# inj_meas.net
KiCad netlist of a schematic drawn in Altium Designer
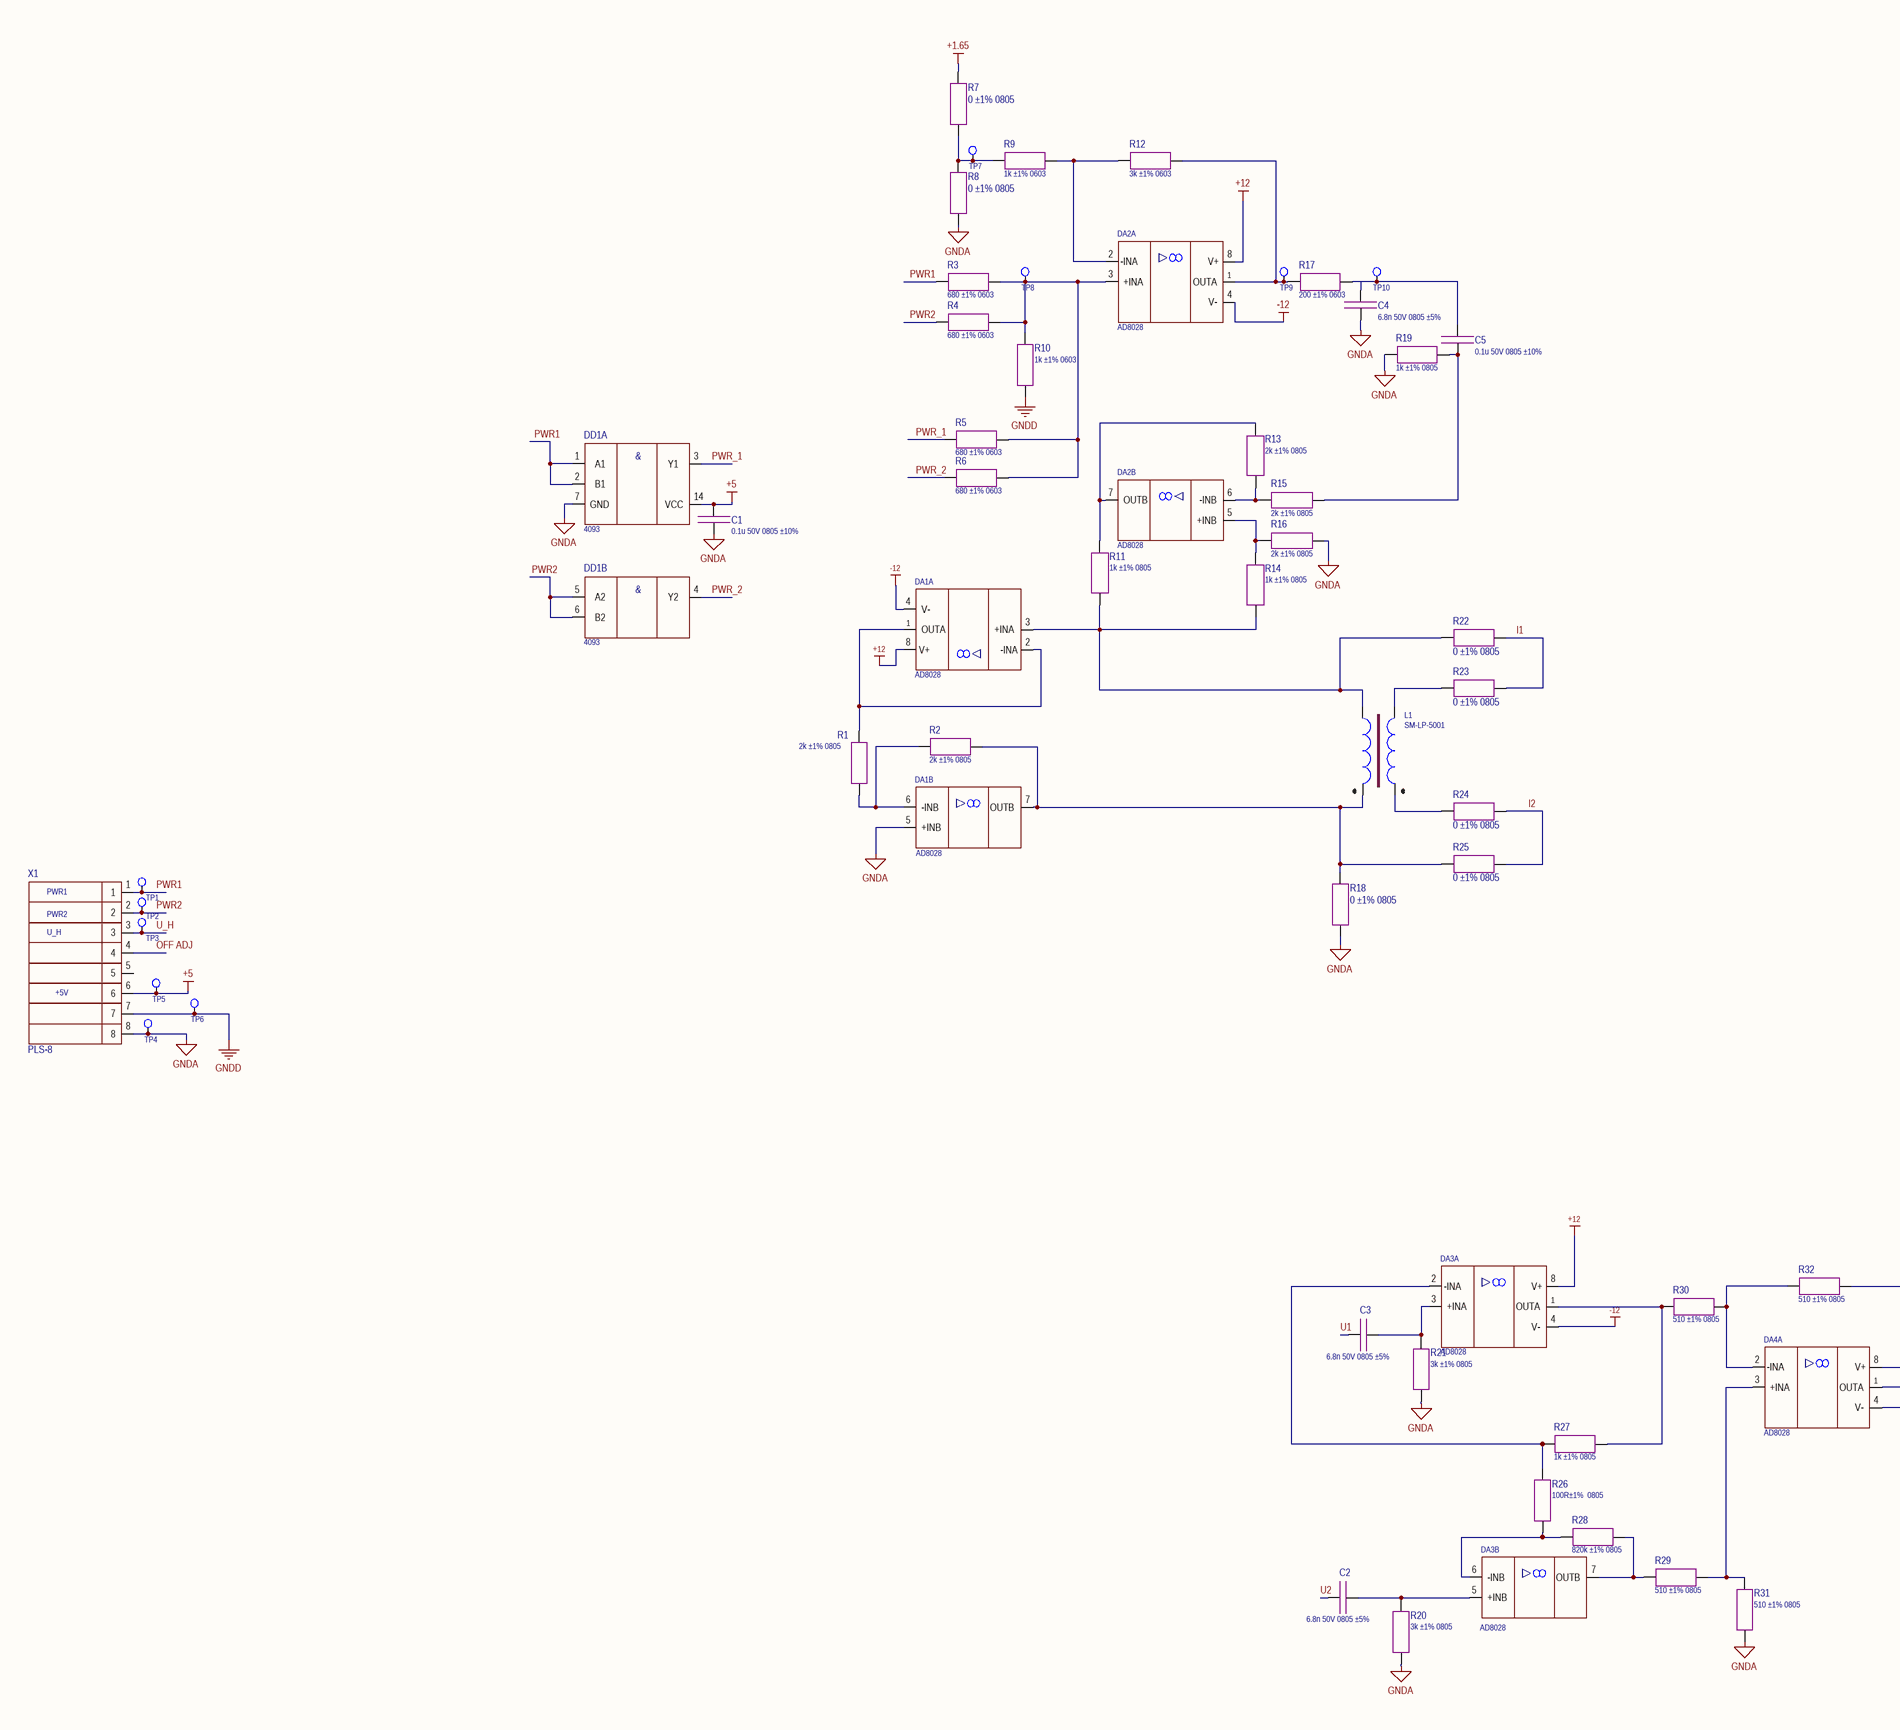
[diagram p0: inj_meas.SchDoc, left]
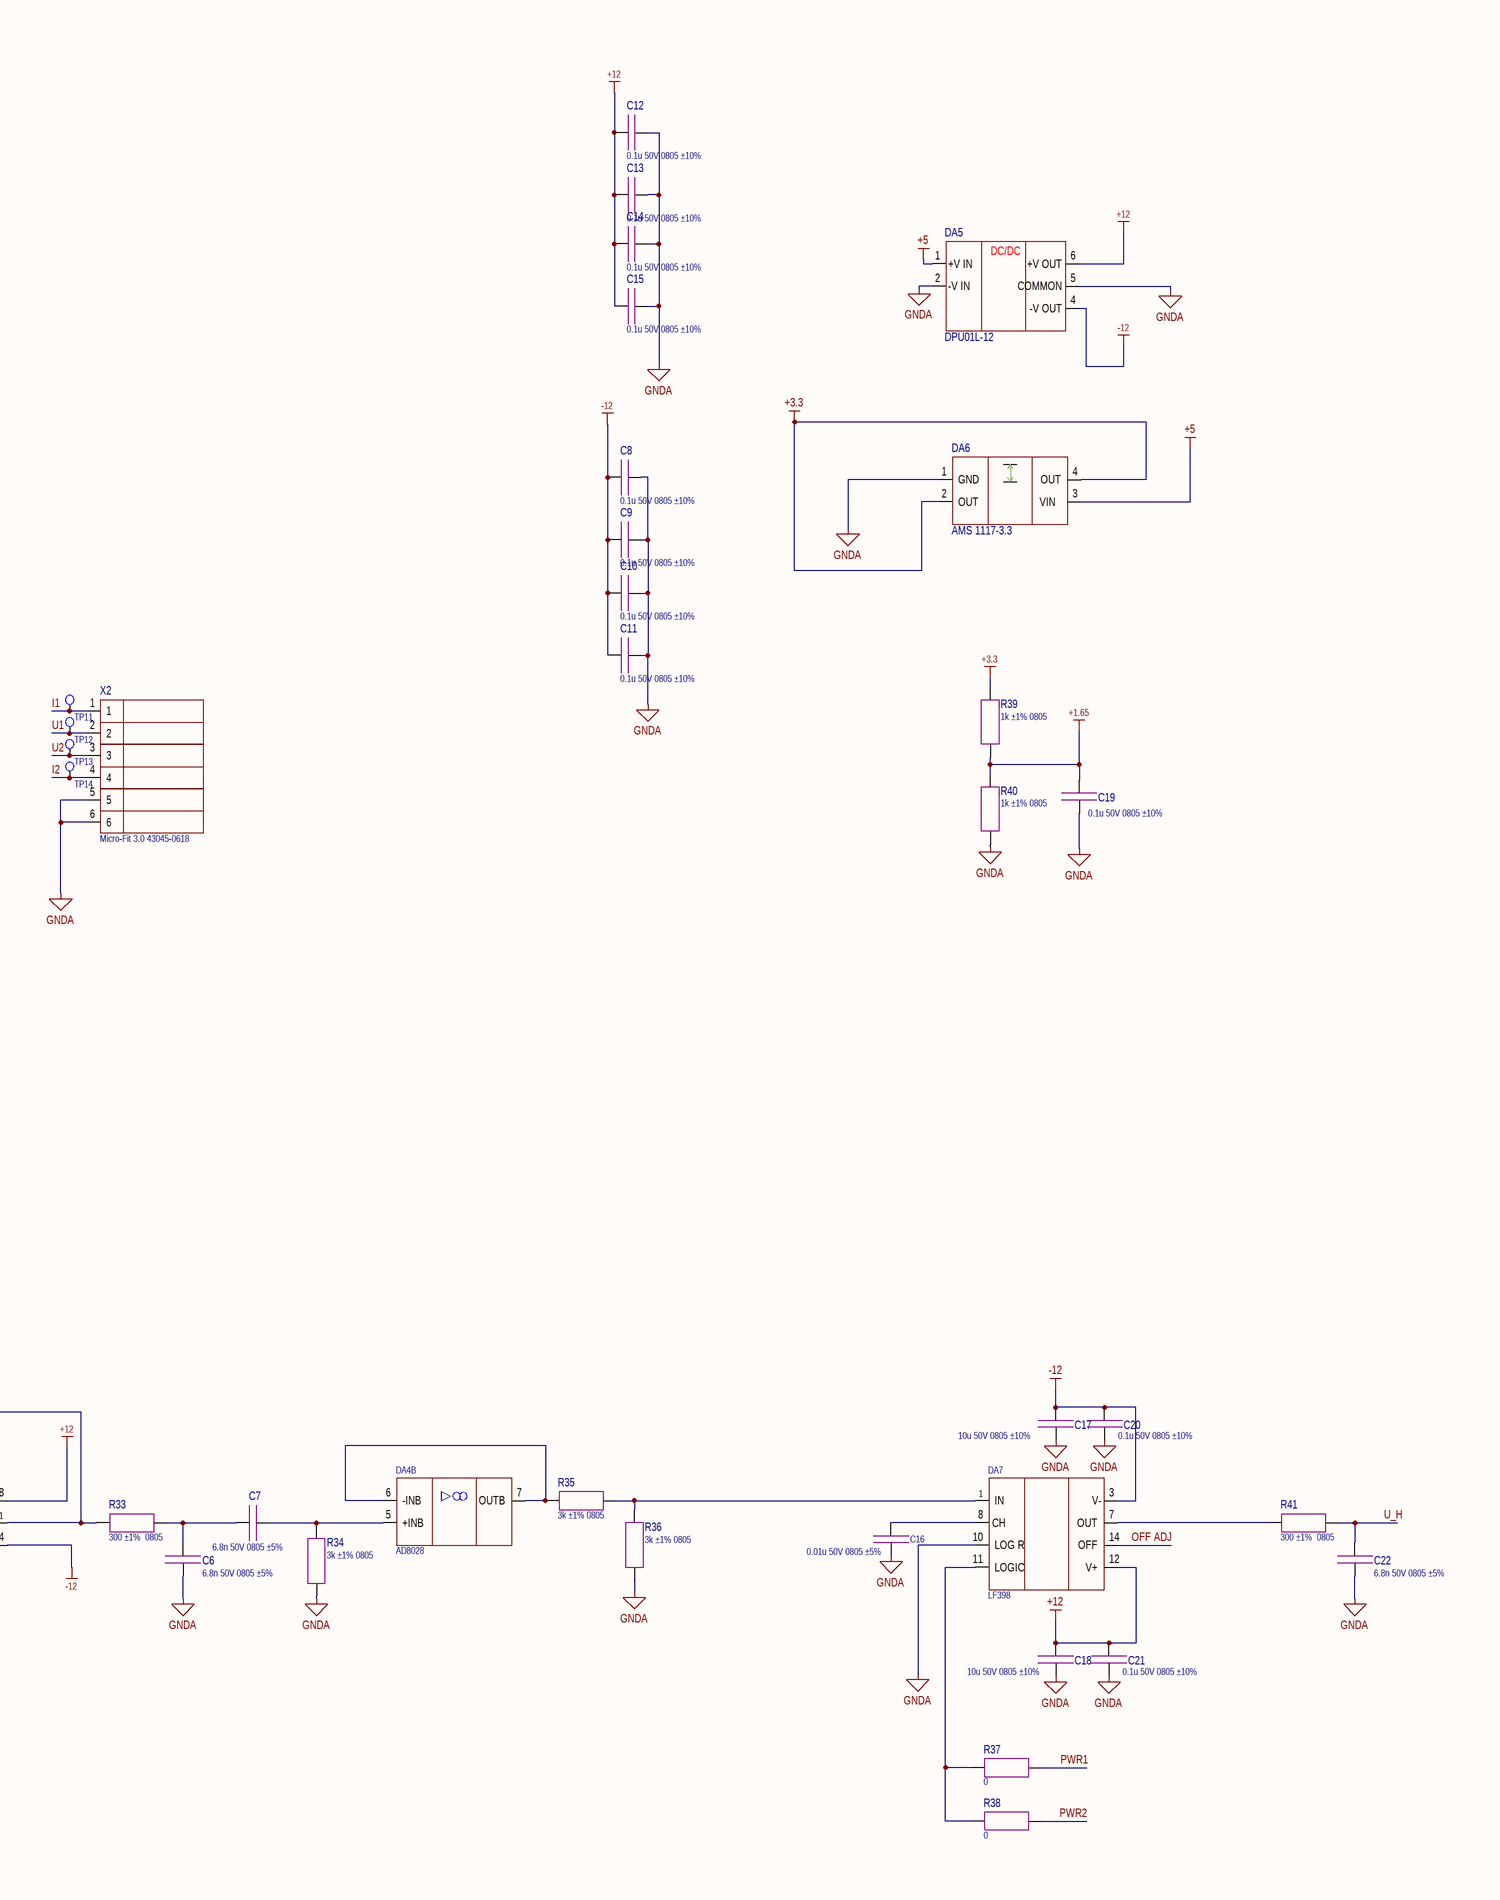
[diagram p1: inj_meas.SchDoc, right]

(export (version "E")
  (design (tool "Eeschema 10.0.6"))
  (components
    (comp (ref "C1")
      (value "0.1u 50V 0805 ±10%")
      (footprint "CAP: SMD 0805 MD IPC 782")
      (libsource (lib "UOMP capacitors") (part "0.1u 50V 0805 ±10%"))
    )
    (comp (ref "C2")
      (value "6.8n 50V 0805 ±5%")
      (footprint "CAP: SMD 0805 MD IPC 782")
      (libsource (lib "UOMP_capacitors") (part "6.8n 50V 0805 ±5%"))
    )
    (comp (ref "C3")
      (value "6.8n 50V 0805 ±5%")
      (footprint "CAP: SMD 0805 MD IPC 782")
      (libsource (lib "UOMP_capacitors") (part "6.8n 50V 0805 ±5%"))
    )
    (comp (ref "C4")
      (value "6.8n 50V 0805 ±5%")
      (footprint "CAP: SMD 0805 MD IPC 782")
      (libsource (lib "UOMP_capacitors") (part "6.8n 50V 0805 ±5%"))
    )
    (comp (ref "C5")
      (value "0.1u 50V 0805 ±10%")
      (footprint "CAP: SMD 0805 MD IPC 782")
      (libsource (lib "UOMP_capacitors") (part "0.1u 50V 0805 ±10%"))
    )
    (comp (ref "C6")
      (value "6.8n 50V 0805 ±5%")
      (footprint "CAP: SMD 0805 MD IPC 782")
      (libsource (lib "UOMP_capacitors") (part "6.8n 50V 0805 ±5%"))
    )
    (comp (ref "C7")
      (value "6.8n 50V 0805 ±5%")
      (footprint "CAP: SMD 0805 MD IPC 782")
      (libsource (lib "UOMP_capacitors") (part "6.8n 50V 0805 ±5%"))
    )
    (comp (ref "C8")
      (value "0.1u 50V 0805 ±10%")
      (footprint "CAP: SMD 0805 MD IPC 782")
      (libsource (lib "UOMP capacitors") (part "0.1u 50V 0805 ±10%"))
    )
    (comp (ref "C9")
      (value "0.1u 50V 0805 ±10%")
      (footprint "CAP: SMD 0805 MD IPC 782")
      (libsource (lib "UOMP capacitors") (part "0.1u 50V 0805 ±10%"))
    )
    (comp (ref "C10")
      (value "0.1u 50V 0805 ±10%")
      (footprint "CAP: SMD 0805 MD IPC 782")
      (libsource (lib "UOMP capacitors") (part "0.1u 50V 0805 ±10%"))
    )
    (comp (ref "C11")
      (value "0.1u 50V 0805 ±10%")
      (footprint "CAP: SMD 0805 MD IPC 782")
      (libsource (lib "UOMP capacitors") (part "0.1u 50V 0805 ±10%"))
    )
    (comp (ref "C12")
      (value "0.1u 50V 0805 ±10%")
      (footprint "CAP: SMD 0805 MD IPC 782")
      (libsource (lib "UOMP capacitors") (part "0.1u 50V 0805 ±10%"))
    )
    (comp (ref "C13")
      (value "0.1u 50V 0805 ±10%")
      (footprint "CAP: SMD 0805 MD IPC 782")
      (libsource (lib "UOMP capacitors") (part "0.1u 50V 0805 ±10%"))
    )
    (comp (ref "C14")
      (value "0.1u 50V 0805 ±10%")
      (footprint "CAP: SMD 0805 MD IPC 782")
      (libsource (lib "UOMP capacitors") (part "0.1u 50V 0805 ±10%"))
    )
    (comp (ref "C15")
      (value "0.1u 50V 0805 ±10%")
      (footprint "CAP: SMD 0805 MD IPC 782")
      (libsource (lib "UOMP capacitors") (part "0.1u 50V 0805 ±10%"))
    )
    (comp (ref "C16")
      (value "0.01u 50V 0805 ±5%")
      (footprint "CAP: SMD 0805 MD IPC 782")
      (libsource (lib "UOMP_capacitors") (part "0.01u 50V 0805 ±5%"))
    )
    (comp (ref "C17")
      (value "10u 50V 0805 ±10%")
      (footprint "CAP: SMD 0805 MD IPC 782")
      (libsource (lib "UOMP_capacitors") (part "10u 50V 0805 ±10%"))
    )
    (comp (ref "C18")
      (value "10u 50V 0805 ±10%")
      (footprint "CAP: SMD 0805 MD IPC 782")
      (libsource (lib "UOMP_capacitors") (part "10u 50V 0805 ±10%"))
    )
    (comp (ref "C19")
      (value "0.1u 50V 0805 ±10%")
      (footprint "CAP: SMD 0805 MD IPC 782")
      (libsource (lib "UOMP capacitors") (part "0.1u 50V 0805 ±10%"))
    )
    (comp (ref "C20")
      (value "0.1u 50V 0805 ±10%")
      (footprint "CAP: SMD 0805 MD IPC 782")
      (libsource (lib "UOMP_capacitors") (part "0.1u 50V 0805 ±10%"))
    )
    (comp (ref "C21")
      (value "0.1u 50V 0805 ±10%")
      (footprint "CAP: SMD 0805 MD IPC 782")
      (libsource (lib "UOMP_capacitors") (part "0.1u 50V 0805 ±10%"))
    )
    (comp (ref "C22")
      (value "6.8n 50V 0805 ±5%")
      (footprint "CAP: SMD 0805 MD IPC 782")
      (libsource (lib "UOMP_capacitors") (part "6.8n 50V 0805 ±5%"))
    )
    (comp (ref "DA1")
      (value "AD8028")
      (footprint "IC: SOIC 8")
      (libsource (lib "THE_BOYS_REO") (part "AD8028_part"))
    )
    (comp (ref "DA2") (value "AD8028") (footprint "IC: SOIC 8") (libsource (lib "") (part "AD8028_part_1")))
    (comp (ref "DA3")
      (value "AD8028")
      (footprint "IC: SOIC 8")
      (libsource (lib "THE_BOYS_REO") (part "AD8028_part"))
    )
    (comp (ref "DA4")
      (value "AD8028")
      (footprint "IC: SOIC 8")
      (libsource (lib "THE_BOYS_REO") (part "AD8028_part"))
    )
    (comp (ref "DA5")
      (value "DPU01L-12")
      (footprint "SIP-6")
      (libsource (lib "UOMP_power") (part "DC-DC{colon} +12/-12V DPU01L-12"))
    )
    (comp (ref "DA6")
      (value "AMS 1117-3.3")
      (footprint "IC: SOT 223")
      (libsource (lib "UOMP_power") (part "LDO{colon} 15-3.3V AMS1117"))
    )
    (comp (ref "DA7")
      (value "LF398")
      (footprint "IC: SOIC 14")
      (libsource (lib "THE_BOYS_REO") (part "LF398MX"))
    )
    (comp (ref "DD1")
      (value "4093")
      (footprint "IC: SOIC 14")
      (description "&")
      (libsource (lib "UOMP_IC") (part "LOGIC{colon} 4093"))
    )
    (comp (ref "L1")
      (value "SM-LP-5001")
      (footprint "IND: SM-LP-5001E")
      (libsource (lib "THE_BOYS_REO") (part "SM-LP-5001"))
    )
    (comp (ref "R1")
      (value "2k ±1% 0805")
      (footprint "RES: SMD 0805 MD IPC 782")
      (libsource (lib "UOMP resistors") (part "2k ±1% 0805"))
    )
    (comp (ref "R2")
      (value "2k ±1% 0805")
      (footprint "RES: SMD 0805 MD IPC 782")
      (libsource (lib "UOMP resistors") (part "2k ±1% 0805"))
    )
    (comp (ref "R3")
      (value "680 ±1% 0603")
      (footprint "RES: SMD 0603 MD IPC 782")
      (libsource (lib "UOMP_resistors") (part "680 ±1% 0603"))
    )
    (comp (ref "R4")
      (value "680 ±1% 0603")
      (footprint "RES: SMD 0603 MD IPC 782")
      (libsource (lib "UOMP_resistors") (part "680 ±1% 0603"))
    )
    (comp (ref "R5")
      (value "680 ±1% 0603")
      (footprint "RES: SMD 0603 MD IPC 782")
      (libsource (lib "UOMP_resistors") (part "680 ±1% 0603"))
    )
    (comp (ref "R6")
      (value "680 ±1% 0603")
      (footprint "RES: SMD 0603 MD IPC 782")
      (libsource (lib "UOMP_resistors") (part "680 ±1% 0603"))
    )
    (comp (ref "R7")
      (value "0 ±1% 0805")
      (footprint "RES: SMD 0805 MD IPC 782")
      (libsource (lib "UOMP_resistors") (part "0 ±1% 0805"))
    )
    (comp (ref "R8")
      (value "0 ±1% 0805")
      (footprint "RES: SMD 0805 MD IPC 782")
      (libsource (lib "UOMP_resistors") (part "0 ±1% 0805"))
    )
    (comp (ref "R9")
      (value "1k ±1% 0603")
      (footprint "RES: SMD 0603 MD IPC 782")
      (libsource (lib "UOMP_resistors") (part "1k ±1% 0603"))
    )
    (comp (ref "R10")
      (value "1k ±1% 0603")
      (footprint "RES: SMD 0603 MD IPC 782")
      (libsource (lib "UOMP_resistors") (part "1k ±1% 0603"))
    )
    (comp (ref "R11")
      (value "1k ±1% 0805")
      (footprint "RES: SMD 0805 MD IPC 782")
      (libsource (lib "UOMP resistors") (part "1k ±1% 0805"))
    )
    (comp (ref "R12")
      (value "3k ±1% 0603")
      (footprint "RES: SMD 0603 MD IPC 782")
      (libsource (lib "UOMP_resistors") (part "3k ±1% 0603"))
    )
    (comp (ref "R13")
      (value "2k ±1% 0805")
      (footprint "RES: SMD 0805 MD IPC 782")
      (libsource (lib "UOMP resistors") (part "2k ±1% 0805"))
    )
    (comp (ref "R14")
      (value "1k ±1% 0805")
      (footprint "RES: SMD 0805 MD IPC 782")
      (libsource (lib "UOMP resistors") (part "1k ±1% 0805"))
    )
    (comp (ref "R15")
      (value "2k ±1% 0805")
      (footprint "RES: SMD 0805 MD IPC 782")
      (libsource (lib "UOMP resistors") (part "2k ±1% 0805"))
    )
    (comp (ref "R16")
      (value "2k ±1% 0805")
      (footprint "RES: SMD 0805 MD IPC 782")
      (libsource (lib "UOMP resistors") (part "2k ±1% 0805"))
    )
    (comp (ref "R17")
      (value "200 ±1% 0603")
      (footprint "RES: SMD 0603 MD IPC 782")
      (libsource (lib "UOMP_resistors") (part "200 ±1% 0603"))
    )
    (comp (ref "R18")
      (value "0 ±1% 0805")
      (footprint "RES: SMD 0805 MD IPC 782")
      (libsource (lib "UOMP_resistors") (part "0 ±1% 0805"))
    )
    (comp (ref "R19")
      (value "1k ±1% 0805")
      (footprint "RES: SMD 0805 MD IPC 782")
      (libsource (lib "UOMP_resistors") (part "1k ±1% 0805"))
    )
    (comp (ref "R20")
      (value "3k ±1% 0805")
      (footprint "RES: SMD 0805 MD IPC 782")
      (libsource (lib "UOMP_resistors") (part "3k ±1% 0805"))
    )
    (comp (ref "R21")
      (value "3k ±1% 0805")
      (footprint "RES: SMD 0805 MD IPC 782")
      (libsource (lib "UOMP_resistors") (part "3k ±1% 0805"))
    )
    (comp (ref "R22")
      (value "0 ±1% 0805")
      (footprint "RES: SMD 0805 MD IPC 782")
      (libsource (lib "UOMP_resistors") (part "0 ±1% 0805"))
    )
    (comp (ref "R23")
      (value "0 ±1% 0805")
      (footprint "RES: SMD 0805 MD IPC 782")
      (libsource (lib "UOMP_resistors") (part "0 ±1% 0805"))
    )
    (comp (ref "R24")
      (value "0 ±1% 0805")
      (footprint "RES: SMD 0805 MD IPC 782")
      (libsource (lib "UOMP_resistors") (part "0 ±1% 0805"))
    )
    (comp (ref "R25")
      (value "0 ±1% 0805")
      (footprint "RES: SMD 0805 MD IPC 782")
      (libsource (lib "UOMP_resistors") (part "0 ±1% 0805"))
    )
    (comp (ref "R26")
      (value "100R±1%  0805")
      (footprint "RES: SMD 0805 MD IPC 782")
      (libsource (lib "UOMP_resistors") (part "100 ±1%  0805"))
    )
    (comp (ref "R27")
      (value "1k ±1% 0805")
      (footprint "RES: SMD 0805 MD IPC 782")
      (libsource (lib "UOMP_resistors") (part "1k ±1% 0805"))
    )
    (comp (ref "R28")
      (value "820k ±1% 0805")
      (footprint "RES: SMD 0805 MD IPC 782")
      (libsource (lib "UOMP_resistors") (part "820k ±1% 0805"))
    )
    (comp (ref "R29")
      (value "510 ±1% 0805")
      (footprint "RES: SMD 0805 MD IPC 782")
      (libsource (lib "UOMP_resistors") (part "510 ±1% 0805"))
    )
    (comp (ref "R30")
      (value "510 ±1% 0805")
      (footprint "RES: SMD 0805 MD IPC 782")
      (libsource (lib "UOMP_resistors") (part "510 ±1% 0805"))
    )
    (comp (ref "R31")
      (value "510 ±1% 0805")
      (footprint "RES: SMD 0805 MD IPC 782")
      (libsource (lib "UOMP_resistors") (part "510 ±1% 0805"))
    )
    (comp (ref "R32")
      (value "510 ±1% 0805")
      (footprint "RES: SMD 0805 MD IPC 782")
      (libsource (lib "UOMP_resistors") (part "510 ±1% 0805"))
    )
    (comp (ref "R33")
      (value "300 ±1%  0805")
      (footprint "RES: SMD 0805 MD IPC 782")
      (libsource (lib "UOMP_resistors") (part "300 ±1%  0805"))
    )
    (comp (ref "R34")
      (value "3k ±1% 0805")
      (footprint "RES: SMD 0805 MD IPC 782")
      (libsource (lib "UOMP_resistors") (part "3k ±1% 0805"))
    )
    (comp (ref "R35")
      (value "3k ±1% 0805")
      (footprint "RES: SMD 0805 MD IPC 782")
      (libsource (lib "UOMP_resistors") (part "3k ±1% 0805"))
    )
    (comp (ref "R36")
      (value "3k ±1% 0805")
      (footprint "RES: SMD 0805 MD IPC 782")
      (libsource (lib "UOMP_resistors") (part "3k ±1% 0805"))
    )
    (comp (ref "R37")
      (value "0")
      (footprint "RES: SMD 0603 MD IPC 782")
      (libsource (lib "UOMP_resistors_0603") (part "0 ±5%"))
    )
    (comp (ref "R38")
      (value "0")
      (footprint "RES: SMD 0603 MD IPC 782")
      (libsource (lib "UOMP_resistors_0603") (part "0 ±5%"))
    )
    (comp (ref "R39")
      (value "1k ±1% 0805")
      (footprint "RES: SMD 0805 MD IPC 782")
      (libsource (lib "UOMP resistors") (part "1k ±1% 0805"))
    )
    (comp (ref "R40")
      (value "1k ±1% 0805")
      (footprint "RES: SMD 0805 MD IPC 782")
      (libsource (lib "UOMP resistors") (part "1k ±1% 0805"))
    )
    (comp (ref "R41")
      (value "300 ±1%  0805")
      (footprint "RES: SMD 0805 MD IPC 782")
      (libsource (lib "UOMP_resistors") (part "300 ±1%  0805"))
    )
    (comp (ref "TP1")
      (value "Test point")
      (footprint "Test Point")
      (libsource (lib "UOMP_primitives") (part "Test point"))
    )
    (comp (ref "TP2")
      (value "Test point")
      (footprint "Test Point")
      (libsource (lib "UOMP_primitives") (part "Test point"))
    )
    (comp (ref "TP3")
      (value "Test point")
      (footprint "Test Point")
      (libsource (lib "UOMP_primitives") (part "Test point"))
    )
    (comp (ref "TP4")
      (value "Test point")
      (footprint "Test Point")
      (libsource (lib "UOMP_primitives") (part "Test point"))
    )
    (comp (ref "TP5")
      (value "Test point")
      (footprint "Test Point")
      (libsource (lib "UOMP_primitives") (part "Test point"))
    )
    (comp (ref "TP6")
      (value "Test point")
      (footprint "Test Point")
      (libsource (lib "UOMP_primitives") (part "Test point"))
    )
    (comp (ref "TP7")
      (value "Test point")
      (footprint "Test Point")
      (libsource (lib "UOMP_primitives") (part "Test point"))
    )
    (comp (ref "TP8")
      (value "Test point")
      (footprint "Test Point")
      (libsource (lib "UOMP_primitives") (part "Test point"))
    )
    (comp (ref "TP9")
      (value "Test point")
      (footprint "Test Point")
      (libsource (lib "UOMP_primitives") (part "Test point"))
    )
    (comp (ref "TP10")
      (value "Test point")
      (footprint "Test Point")
      (libsource (lib "UOMP_primitives") (part "Test point"))
    )
    (comp (ref "TP11")
      (value "Test point")
      (footprint "Test Point")
      (libsource (lib "UOMP_primitives") (part "Test point"))
    )
    (comp (ref "TP12")
      (value "Test point")
      (footprint "Test Point")
      (libsource (lib "UOMP_primitives") (part "Test point"))
    )
    (comp (ref "TP13")
      (value "Test point")
      (footprint "Test Point")
      (libsource (lib "UOMP_primitives") (part "Test point"))
    )
    (comp (ref "TP14")
      (value "Test point")
      (footprint "Test Point")
      (libsource (lib "UOMP_primitives") (part "Test point"))
    )
    (comp (ref "X1")
      (value "PLS-8")
      (footprint "CON: 8PIN PLS-8")
      (libsource (lib "UOMP_connectors") (part "8 pin PLS 8"))
    )
    (comp (ref "X2")
      (value "Micro-Fit 3.0 43045-0618")
      (footprint "CON: 6pin Molex MicroFit 3.0 43045-0618")
      (libsource (lib "UOMP_connectors") (part "6 pin MicroFit DR SMD Molex"))
    )
  )
  (nets
    (net (code "1") (name "+1.65") (class "Default")
      (node (ref "C19") (pin "1") (pinfunction "1_1") (pintype "passive"))
      (node (ref "R39") (pin "1") (pinfunction "1_1") (pintype "passive"))
      (node (ref "R40") (pin "2") (pinfunction "2_2") (pintype "passive"))
      (node (ref "R7") (pin "2") (pinfunction "2_2") (pintype "passive"))
    )
    (net (code "2") (name "+3.3") (class "Default")
      (node (ref "DA6") (pin "2") (pinfunction "OUT_2") (pintype "passive"))
      (node (ref "DA6") (pin "4") (pinfunction "OUT_4") (pintype "passive"))
      (node (ref "R39") (pin "2") (pinfunction "2_2") (pintype "passive"))
    )
    (net (code "3") (name "+5") (class "Default")
      (node (ref "C1") (pin "1") (pinfunction "1_1") (pintype "passive"))
      (node (ref "DA5") (pin "1") (pinfunction "+V_IN_1") (pintype "passive"))
      (node (ref "DA6") (pin "3") (pinfunction "VIN_3") (pintype "passive"))
      (node (ref "DD1") (pin "14") (pinfunction "VCC_14") (pintype "passive"))
      (node (ref "TP5") (pin "1") (pinfunction "1_1") (pintype "passive"))
      (node (ref "X1") (pin "6") (pinfunction "6_6") (pintype "passive"))
    )
    (net (code "4") (name "+12") (class "Default")
      (node (ref "C12") (pin "2") (pinfunction "2_2") (pintype "passive"))
      (node (ref "C13") (pin "2") (pinfunction "2_2") (pintype "passive"))
      (node (ref "C14") (pin "2") (pinfunction "2_2") (pintype "passive"))
      (node (ref "C15") (pin "2") (pinfunction "2_2") (pintype "passive"))
      (node (ref "C18") (pin "1") (pinfunction "1_1") (pintype "passive"))
      (node (ref "C21") (pin "1") (pinfunction "1_1") (pintype "passive"))
      (node (ref "DA1") (pin "8") (pinfunction "V+_8") (pintype "passive"))
      (node (ref "DA2") (pin "8") (pinfunction "V+_8") (pintype "passive"))
      (node (ref "DA3") (pin "8") (pinfunction "V+_8") (pintype "passive"))
      (node (ref "DA4") (pin "8") (pinfunction "V+_8") (pintype "passive"))
      (node (ref "DA5") (pin "6") (pinfunction "+V_OUT_6") (pintype "passive"))
      (node (ref "DA7") (pin "12") (pinfunction "V+_12") (pintype "passive"))
    )
    (net (code "5") (name "-12") (class "Default")
      (node (ref "C10") (pin "2") (pinfunction "2_2") (pintype "passive"))
      (node (ref "C11") (pin "2") (pinfunction "2_2") (pintype "passive"))
      (node (ref "C17") (pin "1") (pinfunction "1_1") (pintype "passive"))
      (node (ref "C20") (pin "1") (pinfunction "1_1") (pintype "passive"))
      (node (ref "C8") (pin "2") (pinfunction "2_2") (pintype "passive"))
      (node (ref "C9") (pin "2") (pinfunction "2_2") (pintype "passive"))
      (node (ref "DA1") (pin "4") (pinfunction "V-_4") (pintype "passive"))
      (node (ref "DA2") (pin "4") (pinfunction "V-_4") (pintype "passive"))
      (node (ref "DA3") (pin "4") (pinfunction "V-_4") (pintype "passive"))
      (node (ref "DA4") (pin "4") (pinfunction "V-_4") (pintype "passive"))
      (node (ref "DA5") (pin "4") (pinfunction "-V_OUT_4") (pintype "passive"))
      (node (ref "DA7") (pin "3") (pinfunction "V-_3") (pintype "passive"))
    )
    (net (code "6") (name "/I1") (class "Default")
      (node (ref "R22") (pin "2") (pinfunction "2_2") (pintype "passive"))
      (node (ref "R23") (pin "2") (pinfunction "2_2") (pintype "passive"))
      (node (ref "TP11") (pin "1") (pinfunction "1_1") (pintype "passive"))
      (node (ref "X2") (pin "1") (pinfunction "1_1") (pintype "passive"))
    )
    (net (code "7") (name "/I2") (class "Default")
      (node (ref "R24") (pin "2") (pinfunction "2_2") (pintype "passive"))
      (node (ref "R25") (pin "2") (pinfunction "2_2") (pintype "passive"))
      (node (ref "TP14") (pin "1") (pinfunction "1_1") (pintype "passive"))
      (node (ref "X2") (pin "4") (pinfunction "4_4") (pintype "passive"))
    )
    (net (code "8") (name "/OFF ADJ") (class "Default")
      (node (ref "DA7") (pin "14") (pinfunction "OFF_14") (pintype "passive"))
      (node (ref "X1") (pin "4") (pinfunction "4_4") (pintype "passive"))
    )
    (net (code "9") (name "/PWR1") (class "Default")
      (node (ref "DD1") (pin "1") (pinfunction "A1_1") (pintype "passive"))
      (node (ref "DD1") (pin "2") (pinfunction "B1_2") (pintype "passive"))
      (node (ref "R3") (pin "1") (pinfunction "1_1") (pintype "passive"))
      (node (ref "R37") (pin "2") (pinfunction "2_2") (pintype "passive"))
      (node (ref "TP1") (pin "1") (pinfunction "1_1") (pintype "passive"))
      (node (ref "X1") (pin "1") (pinfunction "1_1") (pintype "passive"))
    )
    (net (code "10") (name "/PWR2") (class "Default")
      (node (ref "DD1") (pin "5") (pinfunction "A2_5") (pintype "passive"))
      (node (ref "DD1") (pin "6") (pinfunction "B2_6") (pintype "passive"))
      (node (ref "R38") (pin "2") (pinfunction "2_2") (pintype "passive"))
      (node (ref "R4") (pin "1") (pinfunction "1_1") (pintype "passive"))
      (node (ref "TP2") (pin "1") (pinfunction "1_1") (pintype "passive"))
      (node (ref "X1") (pin "2") (pinfunction "2_2") (pintype "passive"))
    )
    (net (code "11") (name "/PWR_1") (class "Default")
      (node (ref "DD1") (pin "3") (pinfunction "Y1_3") (pintype "passive"))
      (node (ref "R5") (pin "1") (pinfunction "1_1") (pintype "passive"))
    )
    (net (code "12") (name "/PWR_2") (class "Default")
      (node (ref "DD1") (pin "4") (pinfunction "Y2_4") (pintype "passive"))
      (node (ref "R6") (pin "1") (pinfunction "1_1") (pintype "passive"))
    )
    (net (code "13") (name "/U1") (class "Default")
      (node (ref "C3") (pin "2") (pinfunction "2_2") (pintype "passive"))
      (node (ref "TP12") (pin "1") (pinfunction "1_1") (pintype "passive"))
      (node (ref "X2") (pin "2") (pinfunction "2_2") (pintype "passive"))
    )
    (net (code "14") (name "/U2") (class "Default")
      (node (ref "C2") (pin "2") (pinfunction "2_2") (pintype "passive"))
      (node (ref "TP13") (pin "1") (pinfunction "1_1") (pintype "passive"))
      (node (ref "X2") (pin "3") (pinfunction "3_3") (pintype "passive"))
    )
    (net (code "15") (name "/U_H") (class "Default")
      (node (ref "C22") (pin "1") (pinfunction "1_1") (pintype "passive"))
      (node (ref "R41") (pin "2") (pinfunction "2_2") (pintype "passive"))
      (node (ref "TP3") (pin "1") (pinfunction "1_1") (pintype "passive"))
      (node (ref "X1") (pin "3") (pinfunction "3_3") (pintype "passive"))
    )
    (net (code "16") (name "GNDA") (class "Default")
      (node (ref "C1") (pin "2") (pinfunction "2_2") (pintype "passive"))
      (node (ref "C10") (pin "1") (pinfunction "1_1") (pintype "passive"))
      (node (ref "C11") (pin "1") (pinfunction "1_1") (pintype "passive"))
      (node (ref "C12") (pin "1") (pinfunction "1_1") (pintype "passive"))
      (node (ref "C13") (pin "1") (pinfunction "1_1") (pintype "passive"))
      (node (ref "C14") (pin "1") (pinfunction "1_1") (pintype "passive"))
      (node (ref "C15") (pin "1") (pinfunction "1_1") (pintype "passive"))
      (node (ref "C16") (pin "2") (pinfunction "2_2") (pintype "passive"))
      (node (ref "C17") (pin "2") (pinfunction "2_2") (pintype "passive"))
      (node (ref "C18") (pin "2") (pinfunction "2_2") (pintype "passive"))
      (node (ref "C19") (pin "2") (pinfunction "2_2") (pintype "passive"))
      (node (ref "C20") (pin "2") (pinfunction "2_2") (pintype "passive"))
      (node (ref "C21") (pin "2") (pinfunction "2_2") (pintype "passive"))
      (node (ref "C22") (pin "2") (pinfunction "2_2") (pintype "passive"))
      (node (ref "C4") (pin "2") (pinfunction "2_2") (pintype "passive"))
      (node (ref "C6") (pin "2") (pinfunction "2_2") (pintype "passive"))
      (node (ref "C8") (pin "1") (pinfunction "1_1") (pintype "passive"))
      (node (ref "C9") (pin "1") (pinfunction "1_1") (pintype "passive"))
      (node (ref "DA1") (pin "5") (pinfunction "+INB_5") (pintype "passive"))
      (node (ref "DA5") (pin "2") (pinfunction "-V_IN_2") (pintype "passive"))
      (node (ref "DA5") (pin "5") (pinfunction "COMMON_5") (pintype "passive"))
      (node (ref "DA6") (pin "1") (pinfunction "GND_1") (pintype "passive"))
      (node (ref "DA7") (pin "10") (pinfunction "LOG_R_10") (pintype "passive"))
      (node (ref "DD1") (pin "7") (pinfunction "GND_7") (pintype "passive"))
      (node (ref "R16") (pin "2") (pinfunction "2_2") (pintype "passive"))
      (node (ref "R18") (pin "1") (pinfunction "1_1") (pintype "passive"))
      (node (ref "R19") (pin "1") (pinfunction "1_1") (pintype "passive"))
      (node (ref "R20") (pin "2") (pinfunction "2_2") (pintype "passive"))
      (node (ref "R21") (pin "2") (pinfunction "2_2") (pintype "passive"))
      (node (ref "R31") (pin "1") (pinfunction "1_1") (pintype "passive"))
      (node (ref "R34") (pin "2") (pinfunction "2_2") (pintype "passive"))
      (node (ref "R36") (pin "1") (pinfunction "1_1") (pintype "passive"))
      (node (ref "R40") (pin "1") (pinfunction "1_1") (pintype "passive"))
      (node (ref "R8") (pin "1") (pinfunction "1_1") (pintype "passive"))
      (node (ref "TP4") (pin "1") (pinfunction "1_1") (pintype "passive"))
      (node (ref "X1") (pin "8") (pinfunction "8_8") (pintype "passive"))
      (node (ref "X2") (pin "5") (pinfunction "5_5") (pintype "passive"))
      (node (ref "X2") (pin "6") (pinfunction "6_6") (pintype "passive"))
    )
    (net (code "17") (name "GNDD") (class "Default")
      (node (ref "R10") (pin "1") (pinfunction "1_1") (pintype "passive"))
      (node (ref "TP6") (pin "1") (pinfunction "1_1") (pintype "passive"))
      (node (ref "X1") (pin "7") (pinfunction "7_7") (pintype "passive"))
    )
    (net (code "18") (name "Net-(C4-Pad1)") (class "Default")
      (node (ref "C4") (pin "1") (pinfunction "1_1") (pintype "passive"))
      (node (ref "C5") (pin "2") (pinfunction "2_2") (pintype "passive"))
      (node (ref "R17") (pin "2") (pinfunction "2_2") (pintype "passive"))
      (node (ref "TP10") (pin "1") (pinfunction "1_1") (pintype "passive"))
    )
    (net (code "19") (name "Net-(C5-Pad1)") (class "Default")
      (node (ref "C5") (pin "1") (pinfunction "1_1") (pintype "passive"))
      (node (ref "R15") (pin "2") (pinfunction "2_2") (pintype "passive"))
      (node (ref "R19") (pin "2") (pinfunction "2_2") (pintype "passive"))
    )
    (net (code "20") (name "Net-(C6-Pad1)") (class "Default")
      (node (ref "C6") (pin "1") (pinfunction "1_1") (pintype "passive"))
      (node (ref "C7") (pin "2") (pinfunction "2_2") (pintype "passive"))
      (node (ref "R33") (pin "2") (pinfunction "2_2") (pintype "passive"))
    )
    (net (code "21") (name "Net-(DA1A-+INA)") (class "Default")
      (node (ref "DA1") (pin "3") (pinfunction "+INA_3") (pintype "passive"))
      (node (ref "L1") (pin "4") (pinfunction "4_4") (pintype "passive"))
      (node (ref "R11") (pin "2") (pinfunction "2_2") (pintype "passive"))
      (node (ref "R14") (pin "1") (pinfunction "1_1") (pintype "passive"))
      (node (ref "R22") (pin "1") (pinfunction "1_1") (pintype "passive"))
    )
    (net (code "22") (name "Net-(DA1A--INA)") (class "Default")
      (node (ref "DA1") (pin "1") (pinfunction "OUTA_1") (pintype "passive"))
      (node (ref "DA1") (pin "2") (pinfunction "-INA_2") (pintype "passive"))
      (node (ref "R1") (pin "1") (pinfunction "1_1") (pintype "passive"))
    )
    (net (code "23") (name "Net-(DA1B--INB)") (class "Default")
      (node (ref "DA1") (pin "6") (pinfunction "-INB_6") (pintype "passive"))
      (node (ref "R1") (pin "2") (pinfunction "2_2") (pintype "passive"))
      (node (ref "R2") (pin "1") (pinfunction "1_1") (pintype "passive"))
    )
    (net (code "24") (name "Net-(DA1B-OUTB)") (class "Default")
      (node (ref "DA1") (pin "7") (pinfunction "OUTB_7") (pintype "passive"))
      (node (ref "L1") (pin "1") (pinfunction "3_1") (pintype "passive"))
      (node (ref "R18") (pin "2") (pinfunction "2_2") (pintype "passive"))
      (node (ref "R2") (pin "2") (pinfunction "2_2") (pintype "passive"))
      (node (ref "R25") (pin "1") (pinfunction "1_1") (pintype "passive"))
    )
    (net (code "25") (name "Net-(DA2A-+INA)") (class "Default")
      (node (ref "DA2") (pin "3") (pinfunction "+INA_3") (pintype "passive"))
      (node (ref "R10") (pin "2") (pinfunction "2_2") (pintype "passive"))
      (node (ref "R3") (pin "2") (pinfunction "2_2") (pintype "passive"))
      (node (ref "R4") (pin "2") (pinfunction "2_2") (pintype "passive"))
      (node (ref "R5") (pin "2") (pinfunction "2_2") (pintype "passive"))
      (node (ref "R6") (pin "2") (pinfunction "2_2") (pintype "passive"))
      (node (ref "TP8") (pin "1") (pinfunction "1_1") (pintype "passive"))
    )
    (net (code "26") (name "Net-(DA2A--INA)") (class "Default")
      (node (ref "DA2") (pin "2") (pinfunction "-INA_2") (pintype "passive"))
      (node (ref "R12") (pin "1") (pinfunction "1_1") (pintype "passive"))
      (node (ref "R9") (pin "2") (pinfunction "2_2") (pintype "passive"))
    )
    (net (code "27") (name "Net-(DA2A-OUTA)") (class "Default")
      (node (ref "DA2") (pin "1") (pinfunction "OUTA_1") (pintype "passive"))
      (node (ref "R12") (pin "2") (pinfunction "2_2") (pintype "passive"))
      (node (ref "R17") (pin "1") (pinfunction "1_1") (pintype "passive"))
      (node (ref "TP9") (pin "1") (pinfunction "1_1") (pintype "passive"))
    )
    (net (code "28") (name "Net-(DA2B-+INB)") (class "Default")
      (node (ref "DA2") (pin "5") (pinfunction "+INB_5") (pintype "passive"))
      (node (ref "R14") (pin "2") (pinfunction "2_2") (pintype "passive"))
      (node (ref "R16") (pin "1") (pinfunction "1_1") (pintype "passive"))
    )
    (net (code "29") (name "Net-(DA2B--INB)") (class "Default")
      (node (ref "DA2") (pin "6") (pinfunction "-INB_6") (pintype "passive"))
      (node (ref "R13") (pin "2") (pinfunction "2_2") (pintype "passive"))
      (node (ref "R15") (pin "1") (pinfunction "1_1") (pintype "passive"))
    )
    (net (code "30") (name "Net-(DA2B-OUTB)") (class "Default")
      (node (ref "DA2") (pin "7") (pinfunction "OUTB_7") (pintype "passive"))
      (node (ref "R11") (pin "1") (pinfunction "1_1") (pintype "passive"))
      (node (ref "R13") (pin "1") (pinfunction "1_1") (pintype "passive"))
    )
    (net (code "31") (name "Net-(DA3A-+INA)") (class "Default")
      (node (ref "C3") (pin "1") (pinfunction "1_1") (pintype "passive"))
      (node (ref "DA3") (pin "3") (pinfunction "+INA_3") (pintype "passive"))
      (node (ref "R21") (pin "1") (pinfunction "1_1") (pintype "passive"))
    )
    (net (code "32") (name "Net-(DA3A--INA)") (class "Default")
      (node (ref "DA3") (pin "2") (pinfunction "-INA_2") (pintype "passive"))
      (node (ref "R26") (pin "2") (pinfunction "2_2") (pintype "passive"))
      (node (ref "R27") (pin "2") (pinfunction "2_2") (pintype "passive"))
    )
    (net (code "33") (name "Net-(DA3A-OUTA)") (class "Default")
      (node (ref "DA3") (pin "1") (pinfunction "OUTA_1") (pintype "passive"))
      (node (ref "R27") (pin "1") (pinfunction "1_1") (pintype "passive"))
      (node (ref "R30") (pin "1") (pinfunction "1_1") (pintype "passive"))
    )
    (net (code "34") (name "Net-(DA3B-+INB)") (class "Default")
      (node (ref "C2") (pin "1") (pinfunction "1_1") (pintype "passive"))
      (node (ref "DA3") (pin "5") (pinfunction "+INB_5") (pintype "passive"))
      (node (ref "R20") (pin "1") (pinfunction "1_1") (pintype "passive"))
    )
    (net (code "35") (name "Net-(DA3B--INB)") (class "Default")
      (node (ref "DA3") (pin "6") (pinfunction "-INB_6") (pintype "passive"))
      (node (ref "R26") (pin "1") (pinfunction "1_1") (pintype "passive"))
      (node (ref "R28") (pin "2") (pinfunction "2_2") (pintype "passive"))
    )
    (net (code "36") (name "Net-(DA3B-OUTB)") (class "Default")
      (node (ref "DA3") (pin "7") (pinfunction "OUTB_7") (pintype "passive"))
      (node (ref "R28") (pin "1") (pinfunction "1_1") (pintype "passive"))
      (node (ref "R29") (pin "1") (pinfunction "1_1") (pintype "passive"))
    )
    (net (code "37") (name "Net-(DA4A-+INA)") (class "Default")
      (node (ref "DA4") (pin "3") (pinfunction "+INA_3") (pintype "passive"))
      (node (ref "R29") (pin "2") (pinfunction "2_2") (pintype "passive"))
      (node (ref "R31") (pin "2") (pinfunction "2_2") (pintype "passive"))
    )
    (net (code "38") (name "Net-(DA4A--INA)") (class "Default")
      (node (ref "DA4") (pin "2") (pinfunction "-INA_2") (pintype "passive"))
      (node (ref "R30") (pin "2") (pinfunction "2_2") (pintype "passive"))
      (node (ref "R32") (pin "1") (pinfunction "1_1") (pintype "passive"))
    )
    (net (code "39") (name "Net-(DA4A-OUTA)") (class "Default")
      (node (ref "DA4") (pin "1") (pinfunction "OUTA_1") (pintype "passive"))
      (node (ref "R32") (pin "2") (pinfunction "2_2") (pintype "passive"))
      (node (ref "R33") (pin "1") (pinfunction "1_1") (pintype "passive"))
    )
    (net (code "40") (name "Net-(DA4B-+INB)") (class "Default")
      (node (ref "C7") (pin "1") (pinfunction "1_1") (pintype "passive"))
      (node (ref "DA4") (pin "5") (pinfunction "+INB_5") (pintype "passive"))
      (node (ref "R34") (pin "1") (pinfunction "1_1") (pintype "passive"))
    )
    (net (code "41") (name "Net-(DA4B--INB)") (class "Default")
      (node (ref "DA4") (pin "6") (pinfunction "-INB_6") (pintype "passive"))
      (node (ref "DA4") (pin "7") (pinfunction "OUTB_7") (pintype "passive"))
      (node (ref "R35") (pin "1") (pinfunction "1_1") (pintype "passive"))
    )
    (net (code "42") (name "Net-(DA7-CH)") (class "Default")
      (node (ref "C16") (pin "1") (pinfunction "1_1") (pintype "passive"))
      (node (ref "DA7") (pin "8") (pinfunction "CH_8") (pintype "passive"))
    )
    (net (code "43") (name "Net-(DA7-IN)") (class "Default")
      (node (ref "DA7") (pin "1") (pinfunction "IN_1") (pintype "passive"))
      (node (ref "R35") (pin "2") (pinfunction "2_2") (pintype "passive"))
      (node (ref "R36") (pin "2") (pinfunction "2_2") (pintype "passive"))
    )
    (net (code "44") (name "Net-(DA7-LOGIC)") (class "Default")
      (node (ref "DA7") (pin "11") (pinfunction "LOGIC_11") (pintype "passive"))
      (node (ref "R37") (pin "1") (pinfunction "1_1") (pintype "passive"))
      (node (ref "R38") (pin "1") (pinfunction "1_1") (pintype "passive"))
    )
    (net (code "45") (name "Net-(DA7-OUT)") (class "Default")
      (node (ref "DA7") (pin "7") (pinfunction "OUT_7") (pintype "passive"))
      (node (ref "R41") (pin "1") (pinfunction "1_1") (pintype "passive"))
    )
    (net (code "46") (name "Net-(L1-1)") (class "Default")
      (node (ref "L1") (pin "2") (pinfunction "1_2") (pintype "passive"))
      (node (ref "R24") (pin "1") (pinfunction "1_1") (pintype "passive"))
    )
    (net (code "47") (name "Net-(L1-6)") (class "Default")
      (node (ref "L1") (pin "3") (pinfunction "6_3") (pintype "passive"))
      (node (ref "R23") (pin "1") (pinfunction "1_1") (pintype "passive"))
    )
    (net (code "48") (name "Net-(R7-Pad1)") (class "Default")
      (node (ref "R7") (pin "1") (pinfunction "1_1") (pintype "passive"))
      (node (ref "R8") (pin "2") (pinfunction "2_2") (pintype "passive"))
      (node (ref "R9") (pin "1") (pinfunction "1_1") (pintype "passive"))
      (node (ref "TP7") (pin "1") (pinfunction "1_1") (pintype "passive"))
    )
    (net (code "49") (name "unconnected-(X1-Pad5)") (class "Default")
      (node (ref "X1") (pin "5") (pinfunction "5_5") (pintype "passive"))
    )
  )
)
